# 1.net
KiCad netlist of a schematic drawn in EasyEDA
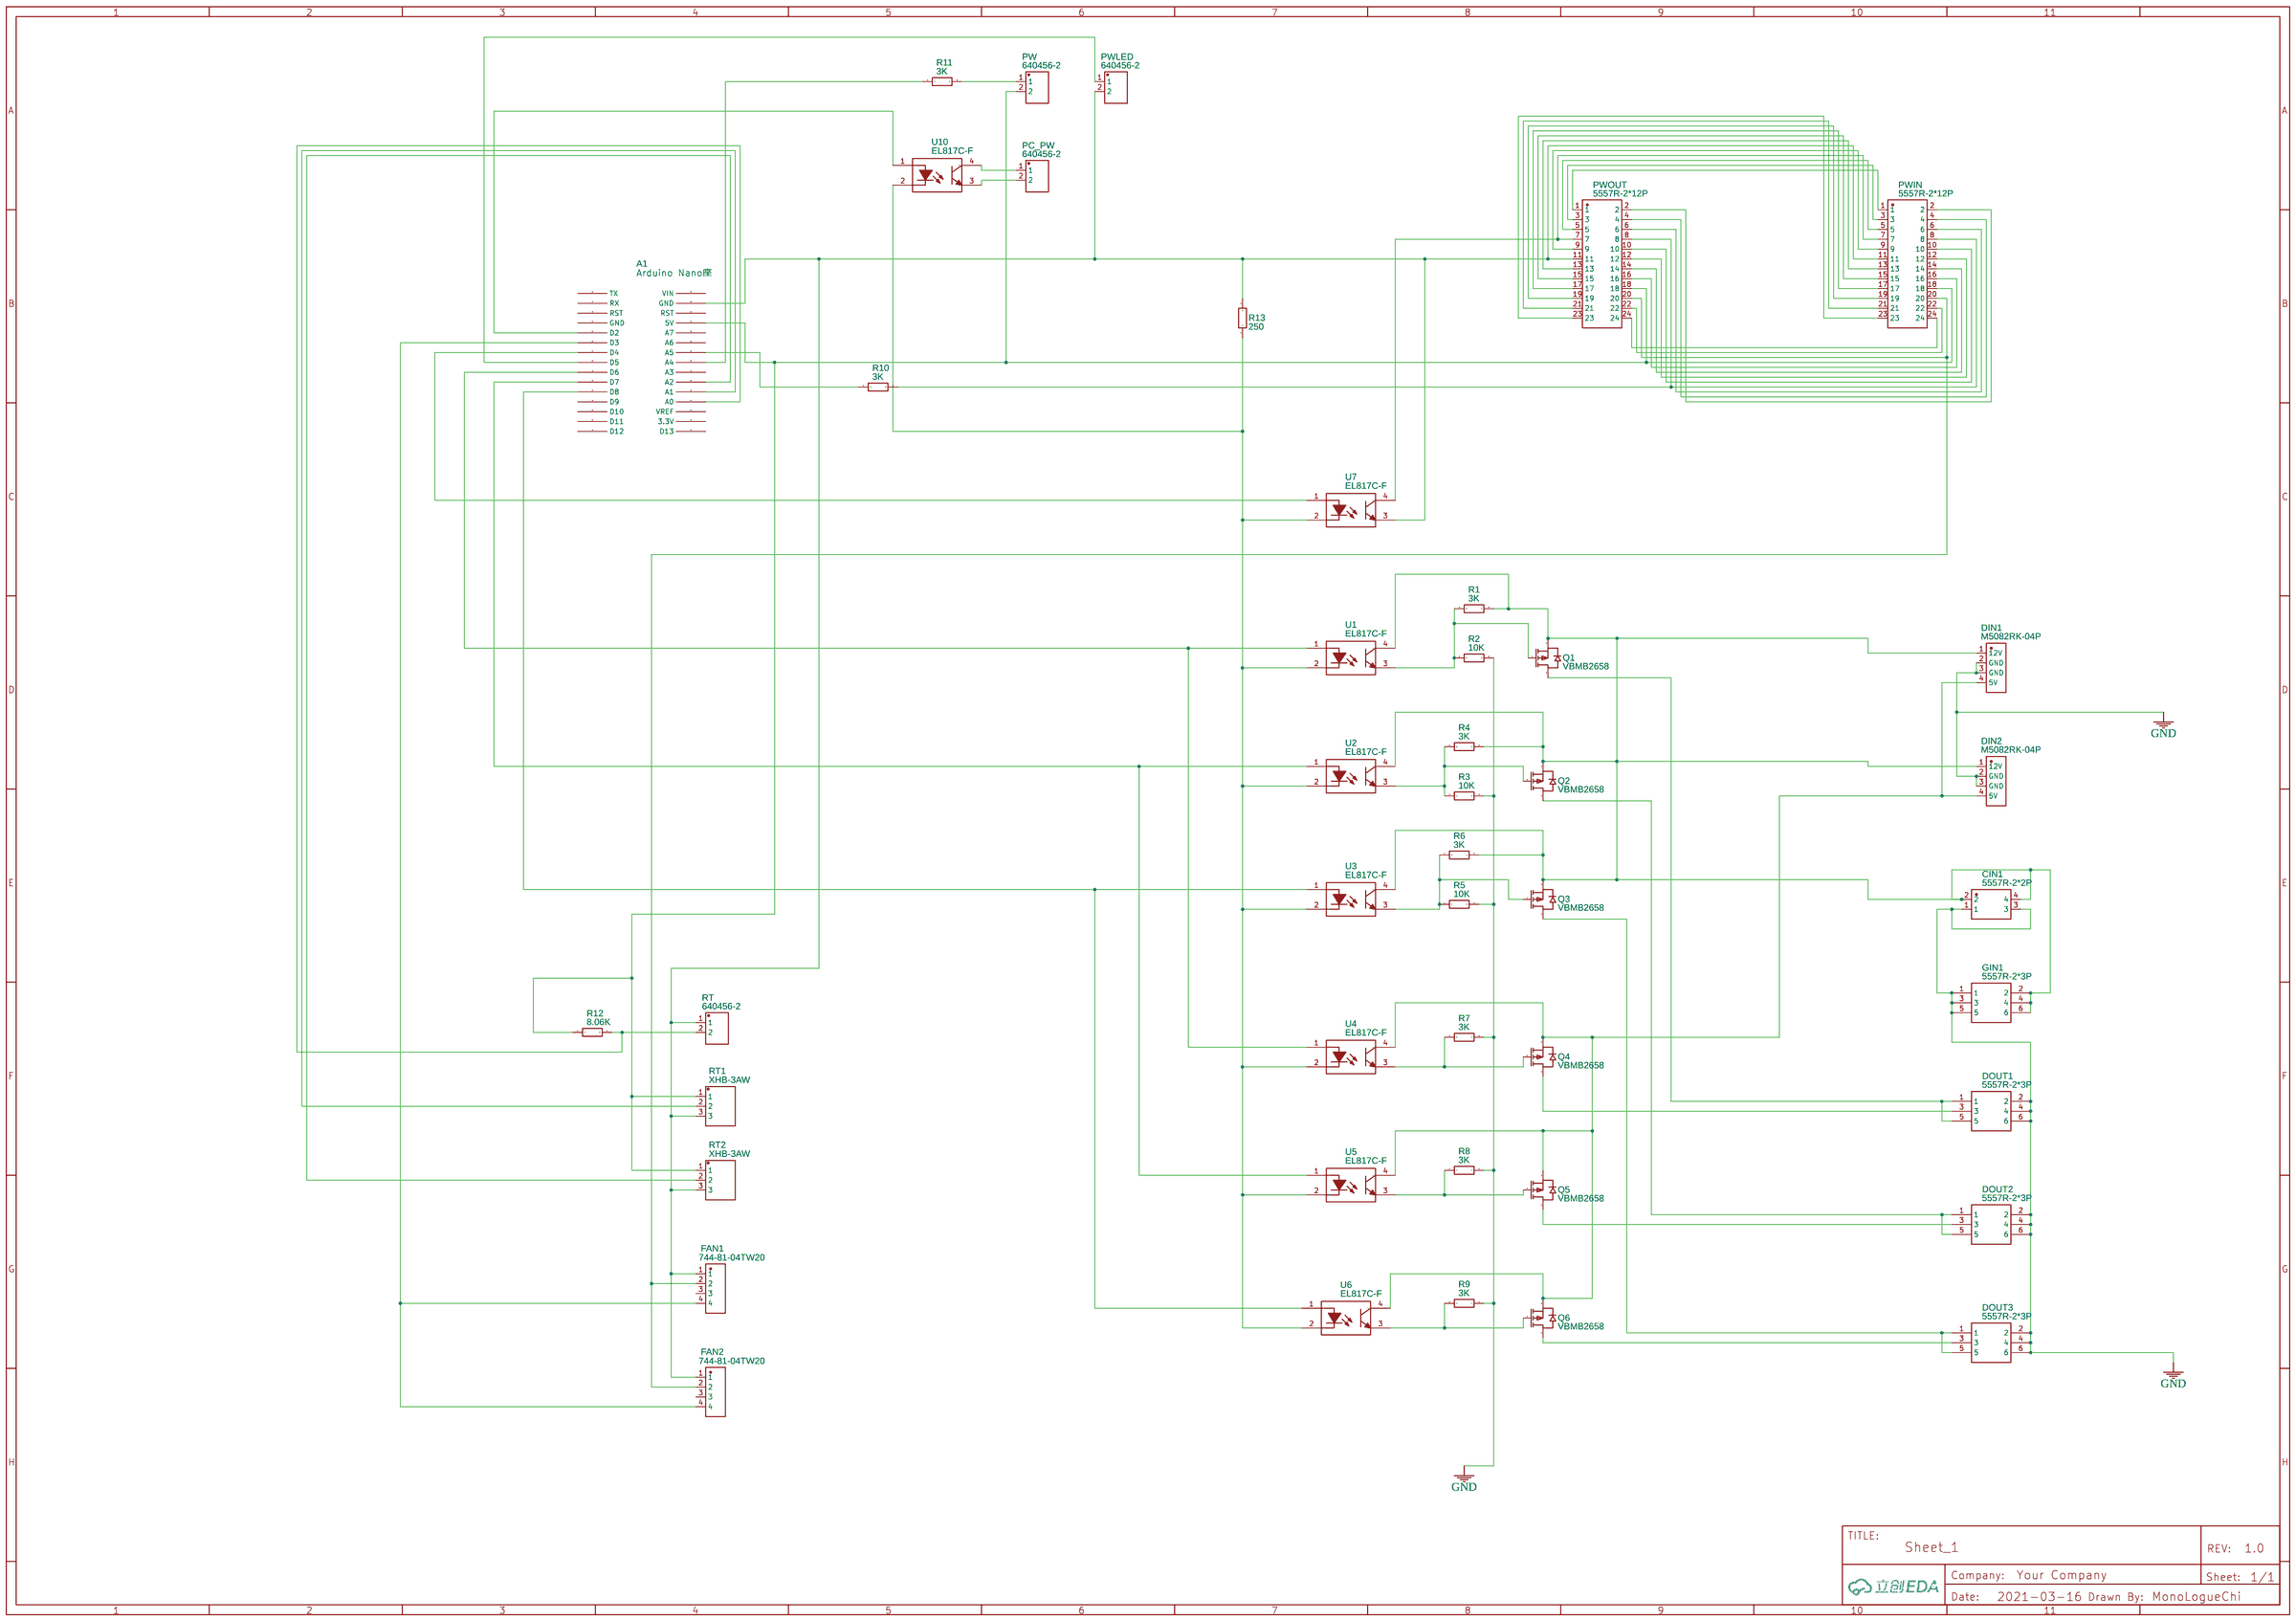
[diagram p0: schematic sheet]

(export (version "E")
  (design (tool "Eeschema 10.0.6"))
  (components
    (comp (ref "A1")
      (value "Arduino Nano座")
      (fields (field (name "BOM_Manufacturer Part") "Arduino Nano"))
      (libsource (lib "") (part "Arduino Nano座"))
    )
    (comp (ref "CIN1")
      (value "5557R-2*2P")
      (fields (field (name "BOM_Supplier Part") "C132446"))
      (libsource (lib "") (part "5557R-2*2P"))
    )
    (comp (ref "DIN1")
      (value "M5082RK-04P")
      (fields (field (name "BOM_Supplier Part") "C492552"))
      (libsource (lib "") (part "M5082RK-04P"))
    )
    (comp (ref "DIN2")
      (value "M5082RK-04P")
      (fields (field (name "BOM_Supplier Part") "C492552"))
      (libsource (lib "") (part "M5082RK-04P"))
    )
    (comp (ref "DOUT1")
      (value "5557R-2*3P")
      (fields (field (name "BOM_Supplier Part") "C124425"))
      (libsource (lib "") (part "5557R-2*3P"))
    )
    (comp (ref "DOUT2")
      (value "5557R-2*3P")
      (fields (field (name "BOM_Supplier Part") "C124425"))
      (libsource (lib "") (part "5557R-2*3P"))
    )
    (comp (ref "DOUT3")
      (value "5557R-2*3P")
      (fields (field (name "BOM_Supplier Part") "C124425"))
      (libsource (lib "") (part "5557R-2*3P"))
    )
    (comp (ref "FAN1")
      (value "744-81-04TW20")
      (fields (field (name "BOM_Supplier Part") "C402778"))
      (libsource (lib "") (part "744-81-04TW20"))
    )
    (comp (ref "FAN2")
      (value "744-81-04TW20")
      (fields (field (name "BOM_Supplier Part") "C402778"))
      (libsource (lib "") (part "744-81-04TW20"))
    )
    (comp (ref "GIN1")
      (value "5557R-2*3P")
      (fields (field (name "BOM_Supplier Part") "C124425"))
      (libsource (lib "") (part "5557R-2*3P_1"))
    )
    (comp (ref "PC_PW")
      (value "640456-2")
      (fields (field (name "BOM_Supplier Part") "C86502"))
      (libsource (lib "") (part "640456-2_1"))
    )
    (comp (ref "PW")
      (value "640456-2")
      (fields (field (name "BOM_Supplier Part") "C86502"))
      (libsource (lib "") (part "640456-2_2"))
    )
    (comp (ref "PWIN")
      (value "5557R-2*12P")
      (fields (field (name "BOM_Supplier Part") "C477841"))
      (libsource (lib "") (part "5557R-2*12P"))
    )
    (comp (ref "PWLED")
      (value "640456-2")
      (fields (field (name "BOM_Supplier Part") "C86502"))
      (libsource (lib "") (part "640456-2"))
    )
    (comp (ref "PWOUT")
      (value "5557R-2*12P")
      (fields (field (name "BOM_Supplier Part") "C477841"))
      (libsource (lib "") (part "5557R-2*12P_1"))
    )
    (comp (ref "Q1")
      (value "VBMB2658")
      (fields (field (name "BOM_Supplier Part") "C481043"))
      (libsource (lib "") (part "VBMB2658_1"))
    )
    (comp (ref "Q2")
      (value "VBMB2658")
      (fields (field (name "BOM_Supplier Part") "C481043"))
      (libsource (lib "") (part "VBMB2658_1"))
    )
    (comp (ref "Q3")
      (value "VBMB2658")
      (fields (field (name "BOM_Supplier Part") "C481043"))
      (libsource (lib "") (part "VBMB2658"))
    )
    (comp (ref "Q4")
      (value "VBMB2658")
      (fields (field (name "BOM_Supplier Part") "C481043"))
      (libsource (lib "") (part "VBMB2658"))
    )
    (comp (ref "Q5")
      (value "VBMB2658")
      (fields (field (name "BOM_Supplier Part") "C481043"))
      (libsource (lib "") (part "VBMB2658"))
    )
    (comp (ref "Q6")
      (value "VBMB2658")
      (fields (field (name "BOM_Supplier Part") "C481043"))
      (libsource (lib "") (part "VBMB2658"))
    )
    (comp (ref "R1")
      (value "3K")
      (fields
        (field (name "BOM_Manufacturer Part") "MFR0W4F3001A50")
        (field (name "BOM_Supplier Part") "C58606")
      )
      (libsource (lib "") (part "MFR0W4F3001A50"))
    )
    (comp (ref "R2")
      (value "10K")
      (fields
        (field (name "BOM_Manufacturer Part") "MFR0W4F1002A50")
        (field (name "BOM_Supplier Part") "C57436")
      )
      (libsource (lib "") (part "MFR0W4F1002A50"))
    )
    (comp (ref "R3")
      (value "10K")
      (fields
        (field (name "BOM_Manufacturer Part") "MFR0W4F1002A50")
        (field (name "BOM_Supplier Part") "C57436")
      )
      (libsource (lib "") (part "MFR0W4F1002A50"))
    )
    (comp (ref "R4")
      (value "3K")
      (fields
        (field (name "BOM_Manufacturer Part") "MFR0W4F3001A50")
        (field (name "BOM_Supplier Part") "C58606")
      )
      (libsource (lib "") (part "MFR0W4F3001A50"))
    )
    (comp (ref "R5")
      (value "10K")
      (fields
        (field (name "BOM_Manufacturer Part") "MFR0W4F1002A50")
        (field (name "BOM_Supplier Part") "C57436")
      )
      (libsource (lib "") (part "MFR0W4F1002A50"))
    )
    (comp (ref "R6")
      (value "3K")
      (fields
        (field (name "BOM_Manufacturer Part") "MFR0W4F3001A50")
        (field (name "BOM_Supplier Part") "C58606")
      )
      (libsource (lib "") (part "MFR0W4F3001A50"))
    )
    (comp (ref "R7")
      (value "3K")
      (fields
        (field (name "BOM_Manufacturer Part") "MFR0W4F3001A50")
        (field (name "BOM_Supplier Part") "C58606")
      )
      (libsource (lib "") (part "MFR0W4F3001A50"))
    )
    (comp (ref "R8")
      (value "3K")
      (fields
        (field (name "BOM_Manufacturer Part") "MFR0W4F3001A50")
        (field (name "BOM_Supplier Part") "C58606")
      )
      (libsource (lib "") (part "MFR0W4F3001A50"))
    )
    (comp (ref "R9")
      (value "3K")
      (fields
        (field (name "BOM_Manufacturer Part") "MFR0W4F3001A50")
        (field (name "BOM_Supplier Part") "C58606")
      )
      (libsource (lib "") (part "MFR0W4F3001A50"))
    )
    (comp (ref "R10")
      (value "3K")
      (fields
        (field (name "BOM_Manufacturer Part") "MFR0W4F3001A50")
        (field (name "BOM_Supplier Part") "C58606")
      )
      (libsource (lib "") (part "MFR0W4F3001A50"))
    )
    (comp (ref "R11")
      (value "3K")
      (fields
        (field (name "BOM_Manufacturer Part") "MFR0W4F3001A50")
        (field (name "BOM_Supplier Part") "C58606")
      )
      (libsource (lib "") (part "MFR0W4F3001A50"))
    )
    (comp (ref "R12")
      (value "8.06K")
      (fields
        (field (name "BOM_Manufacturer Part") "RN16T28061F")
        (field (name "BOM_Supplier Part") "C172591")
      )
      (libsource (lib "") (part "RN16T28061F"))
    )
    (comp (ref "R13")
      (value "250")
      (fields
        (field (name "BOM_Manufacturer Part") "MFR-25FTE52-250R")
        (field (name "BOM_Supplier Part") "C172991")
      )
      (libsource (lib "") (part "MFR-25FTE52-250R"))
    )
    (comp (ref "RT")
      (value "640456-2")
      (fields (field (name "BOM_Supplier Part") "C86502"))
      (libsource (lib "") (part "640456-2_3"))
    )
    (comp (ref "RT1")
      (value "XHB-3AW")
      (fields (field (name "BOM_Supplier Part") "C95477"))
      (libsource (lib "") (part "XHB-3AW"))
    )
    (comp (ref "RT2")
      (value "XHB-3AW")
      (fields (field (name "BOM_Supplier Part") "C95477"))
      (libsource (lib "") (part "XHB-3AW"))
    )
    (comp (ref "U1")
      (value "EL817C-F")
      (fields (field (name "BOM_Supplier Part") "C5352"))
      (libsource (lib "") (part "EL817C-F"))
    )
    (comp (ref "U2")
      (value "EL817C-F")
      (fields (field (name "BOM_Supplier Part") "C5352"))
      (libsource (lib "") (part "EL817C-F"))
    )
    (comp (ref "U3")
      (value "EL817C-F")
      (fields (field (name "BOM_Supplier Part") "C5352"))
      (libsource (lib "") (part "EL817C-F"))
    )
    (comp (ref "U4")
      (value "EL817C-F")
      (fields (field (name "BOM_Supplier Part") "C5352"))
      (libsource (lib "") (part "EL817C-F"))
    )
    (comp (ref "U5")
      (value "EL817C-F")
      (fields (field (name "BOM_Supplier Part") "C5352"))
      (libsource (lib "") (part "EL817C-F"))
    )
    (comp (ref "U6")
      (value "EL817C-F")
      (fields (field (name "BOM_Supplier Part") "C5352"))
      (libsource (lib "") (part "EL817C-F"))
    )
    (comp (ref "U7")
      (value "EL817C-F")
      (fields (field (name "BOM_Supplier Part") "C5352"))
      (libsource (lib "") (part "EL817C-F"))
    )
    (comp (ref "U10")
      (value "EL817C-F")
      (fields (field (name "BOM_Supplier Part") "C5352"))
      (libsource (lib "") (part "EL817C-F"))
    )
  )
  (nets
    (net (code "1") (name "GND") (class "Default")
      (node (ref "CIN1") (pin "1") (pinfunction "1_1") (pintype "unspecified"))
      (node (ref "CIN1") (pin "3") (pinfunction "3_3") (pintype "unspecified"))
      (node (ref "DIN1") (pin "2") (pinfunction "GND_2") (pintype "unspecified"))
      (node (ref "DIN1") (pin "3") (pinfunction "GND_3") (pintype "unspecified"))
      (node (ref "DIN2") (pin "2") (pinfunction "GND_2") (pintype "unspecified"))
      (node (ref "DIN2") (pin "3") (pinfunction "GND_3") (pintype "unspecified"))
      (node (ref "DOUT1") (pin "2") (pinfunction "2_2") (pintype "unspecified"))
      (node (ref "DOUT1") (pin "4") (pinfunction "4_4") (pintype "unspecified"))
      (node (ref "DOUT1") (pin "6") (pinfunction "6_6") (pintype "unspecified"))
      (node (ref "DOUT2") (pin "2") (pinfunction "2_2") (pintype "unspecified"))
      (node (ref "DOUT2") (pin "4") (pinfunction "4_4") (pintype "unspecified"))
      (node (ref "DOUT2") (pin "6") (pinfunction "6_6") (pintype "unspecified"))
      (node (ref "DOUT3") (pin "2") (pinfunction "2_2") (pintype "unspecified"))
      (node (ref "DOUT3") (pin "4") (pinfunction "4_4") (pintype "unspecified"))
      (node (ref "DOUT3") (pin "6") (pinfunction "6_6") (pintype "unspecified"))
      (node (ref "GIN1") (pin "1") (pinfunction "1_1") (pintype "unspecified"))
      (node (ref "GIN1") (pin "3") (pinfunction "3_3") (pintype "unspecified"))
      (node (ref "GIN1") (pin "5") (pinfunction "5_5") (pintype "unspecified"))
      (node (ref "R2") (pin "2") (pinfunction "2_2") (pintype "input"))
      (node (ref "R3") (pin "2") (pinfunction "2_2") (pintype "input"))
      (node (ref "R5") (pin "2") (pinfunction "2_2") (pintype "input"))
      (node (ref "R7") (pin "2") (pinfunction "2_2") (pintype "input"))
      (node (ref "R8") (pin "2") (pinfunction "2_2") (pintype "input"))
      (node (ref "R9") (pin "2") (pinfunction "2_2") (pintype "input"))
    )
    (net (code "2") (name "Net-(A1-5V)") (class "Default")
      (node (ref "A1") (pin "27") (pinfunction "5V_27") (pintype "unspecified"))
      (node (ref "PW") (pin "2") (pinfunction "2_2") (pintype "unspecified"))
      (node (ref "PWIN") (pin "18") (pinfunction "18_18") (pintype "unspecified"))
      (node (ref "PWOUT") (pin "18") (pinfunction "18_18") (pintype "unspecified"))
      (node (ref "R12") (pin "1") (pinfunction "1_1") (pintype "unspecified"))
      (node (ref "RT1") (pin "1") (pinfunction "1_1") (pintype "unspecified"))
      (node (ref "RT2") (pin "1") (pinfunction "1_1") (pintype "unspecified"))
    )
    (net (code "3") (name "Net-(A1-A0)") (class "Default")
      (node (ref "A1") (pin "19") (pinfunction "A0_19") (pintype "unspecified"))
      (node (ref "R12") (pin "2") (pinfunction "2_2") (pintype "unspecified"))
      (node (ref "RT") (pin "2") (pinfunction "2_2") (pintype "unspecified"))
    )
    (net (code "4") (name "Net-(A1-A1)") (class "Default")
      (node (ref "A1") (pin "20") (pinfunction "A1_20") (pintype "unspecified"))
      (node (ref "RT1") (pin "2") (pinfunction "2_2") (pintype "unspecified"))
    )
    (net (code "5") (name "Net-(A1-A2)") (class "Default")
      (node (ref "A1") (pin "21") (pinfunction "A2_21") (pintype "unspecified"))
      (node (ref "RT2") (pin "2") (pinfunction "2_2") (pintype "unspecified"))
    )
    (net (code "6") (name "Net-(A1-A4)") (class "Default")
      (node (ref "A1") (pin "23") (pinfunction "A4_23") (pintype "unspecified"))
      (node (ref "R11") (pin "1") (pinfunction "1_1") (pintype "input"))
    )
    (net (code "7") (name "Net-(A1-A5)") (class "Default")
      (node (ref "A1") (pin "24") (pinfunction "A5_24") (pintype "unspecified"))
      (node (ref "R10") (pin "1") (pinfunction "1_1") (pintype "input"))
    )
    (net (code "8") (name "Net-(A1-D2)") (class "Default")
      (node (ref "A1") (pin "5") (pinfunction "D2_5") (pintype "unspecified"))
      (node (ref "U10") (pin "1") (pinfunction "1_1") (pintype "unspecified"))
    )
    (net (code "9") (name "Net-(A1-D3)") (class "Default")
      (node (ref "A1") (pin "6") (pinfunction "D3_6") (pintype "unspecified"))
      (node (ref "FAN1") (pin "4") (pinfunction "4_4") (pintype "unspecified"))
      (node (ref "FAN2") (pin "4") (pinfunction "4_4") (pintype "unspecified"))
    )
    (net (code "10") (name "Net-(A1-D4)") (class "Default")
      (node (ref "A1") (pin "7") (pinfunction "D4_7") (pintype "unspecified"))
      (node (ref "U7") (pin "1") (pinfunction "1_1") (pintype "unspecified"))
    )
    (net (code "11") (name "Net-(A1-D5)") (class "Default")
      (node (ref "A1") (pin "8") (pinfunction "D5_8") (pintype "unspecified"))
      (node (ref "PWLED") (pin "1") (pinfunction "1_1") (pintype "unspecified"))
    )
    (net (code "12") (name "Net-(A1-D6)") (class "Default")
      (node (ref "A1") (pin "9") (pinfunction "D6_9") (pintype "unspecified"))
      (node (ref "U1") (pin "1") (pinfunction "1_1") (pintype "unspecified"))
      (node (ref "U4") (pin "1") (pinfunction "1_1") (pintype "unspecified"))
    )
    (net (code "13") (name "Net-(A1-D7)") (class "Default")
      (node (ref "A1") (pin "10") (pinfunction "D7_10") (pintype "unspecified"))
      (node (ref "U2") (pin "1") (pinfunction "1_1") (pintype "unspecified"))
      (node (ref "U5") (pin "1") (pinfunction "1_1") (pintype "unspecified"))
    )
    (net (code "14") (name "Net-(A1-D8)") (class "Default")
      (node (ref "A1") (pin "11") (pinfunction "D8_11") (pintype "unspecified"))
      (node (ref "U3") (pin "1") (pinfunction "1_1") (pintype "unspecified"))
      (node (ref "U6") (pin "1") (pinfunction "1_1") (pintype "unspecified"))
    )
    (net (code "15") (name "Net-(A1-GND-Pad29)") (class "Default")
      (node (ref "A1") (pin "29") (pinfunction "GND_29") (pintype "unspecified"))
      (node (ref "FAN1") (pin "1") (pinfunction "1_1") (pintype "unspecified"))
      (node (ref "FAN2") (pin "1") (pinfunction "1_1") (pintype "unspecified"))
      (node (ref "PWIN") (pin "11") (pinfunction "11_11") (pintype "unspecified"))
      (node (ref "PWLED") (pin "2") (pinfunction "2_2") (pintype "unspecified"))
      (node (ref "PWOUT") (pin "11") (pinfunction "11_11") (pintype "unspecified"))
      (node (ref "R13") (pin "1") (pinfunction "1_1") (pintype "unspecified"))
      (node (ref "RT") (pin "1") (pinfunction "1_1") (pintype "unspecified"))
      (node (ref "RT1") (pin "3") (pinfunction "3_3") (pintype "unspecified"))
      (node (ref "RT2") (pin "3") (pinfunction "3_3") (pintype "unspecified"))
      (node (ref "U7") (pin "3") (pinfunction "3_3") (pintype "unspecified"))
    )
    (net (code "16") (name "Net-(DIN1-5V)") (class "Default")
      (node (ref "DIN1") (pin "4") (pinfunction "5V_4") (pintype "unspecified"))
      (node (ref "DIN2") (pin "4") (pinfunction "5V_4") (pintype "unspecified"))
      (node (ref "Q4") (pin "3") (pinfunction "S_3") (pintype "unspecified"))
      (node (ref "Q5") (pin "3") (pinfunction "S_3") (pintype "unspecified"))
      (node (ref "Q6") (pin "3") (pinfunction "S_3") (pintype "unspecified"))
      (node (ref "U4") (pin "4") (pinfunction "4_4") (pintype "unspecified"))
      (node (ref "U5") (pin "4") (pinfunction "4_4") (pintype "unspecified"))
      (node (ref "U6") (pin "4") (pinfunction "4_4") (pintype "unspecified"))
    )
    (net (code "17") (name "Net-(DIN1-12V)") (class "Default")
      (node (ref "CIN1") (pin "2") (pinfunction "2_2") (pintype "unspecified"))
      (node (ref "CIN1") (pin "4") (pinfunction "4_4") (pintype "unspecified"))
      (node (ref "DIN1") (pin "1") (pinfunction "12V_1") (pintype "unspecified"))
      (node (ref "DIN2") (pin "1") (pinfunction "12V_1") (pintype "unspecified"))
      (node (ref "GIN1") (pin "2") (pinfunction "2_2") (pintype "unspecified"))
      (node (ref "GIN1") (pin "4") (pinfunction "4_4") (pintype "unspecified"))
      (node (ref "GIN1") (pin "6") (pinfunction "6_6") (pintype "unspecified"))
      (node (ref "Q1") (pin "3") (pinfunction "S_3") (pintype "unspecified"))
      (node (ref "Q2") (pin "3") (pinfunction "S_3") (pintype "unspecified"))
      (node (ref "Q3") (pin "3") (pinfunction "S_3") (pintype "unspecified"))
      (node (ref "R1") (pin "2") (pinfunction "2_2") (pintype "input"))
      (node (ref "R4") (pin "2") (pinfunction "2_2") (pintype "input"))
      (node (ref "R6") (pin "2") (pinfunction "2_2") (pintype "input"))
      (node (ref "U1") (pin "4") (pinfunction "4_4") (pintype "unspecified"))
      (node (ref "U2") (pin "4") (pinfunction "4_4") (pintype "unspecified"))
      (node (ref "U3") (pin "4") (pinfunction "4_4") (pintype "unspecified"))
    )
    (net (code "18") (name "Net-(FAN1-Pad2)") (class "Default")
      (node (ref "FAN1") (pin "2") (pinfunction "2_2") (pintype "unspecified"))
      (node (ref "FAN2") (pin "2") (pinfunction "2_2") (pintype "unspecified"))
      (node (ref "PWIN") (pin "20") (pinfunction "20_20") (pintype "unspecified"))
      (node (ref "PWOUT") (pin "20") (pinfunction "20_20") (pintype "unspecified"))
    )
    (net (code "19") (name "Net-(PC_PW-Pad1)") (class "Default")
      (node (ref "PC_PW") (pin "1") (pinfunction "1_1") (pintype "unspecified"))
      (node (ref "U10") (pin "4") (pinfunction "4_4") (pintype "unspecified"))
    )
    (net (code "20") (name "Net-(PC_PW-Pad2)") (class "Default")
      (node (ref "PC_PW") (pin "2") (pinfunction "2_2") (pintype "unspecified"))
      (node (ref "U10") (pin "3") (pinfunction "3_3") (pintype "unspecified"))
    )
    (net (code "21") (name "Net-(PW-Pad1)") (class "Default")
      (node (ref "PW") (pin "1") (pinfunction "1_1") (pintype "unspecified"))
      (node (ref "R11") (pin "2") (pinfunction "2_2") (pintype "input"))
    )
    (net (code "22") (name "Net-(PWIN-Pad1)") (class "Default")
      (node (ref "PWIN") (pin "1") (pinfunction "1_1") (pintype "unspecified"))
      (node (ref "PWOUT") (pin "1") (pinfunction "1_1") (pintype "unspecified"))
    )
    (net (code "23") (name "Net-(PWIN-Pad2)") (class "Default")
      (node (ref "PWIN") (pin "2") (pinfunction "2_2") (pintype "unspecified"))
      (node (ref "PWOUT") (pin "2") (pinfunction "2_2") (pintype "unspecified"))
    )
    (net (code "24") (name "Net-(PWIN-Pad3)") (class "Default")
      (node (ref "PWIN") (pin "3") (pinfunction "3_3") (pintype "unspecified"))
      (node (ref "PWOUT") (pin "3") (pinfunction "3_3") (pintype "unspecified"))
    )
    (net (code "25") (name "Net-(PWIN-Pad4)") (class "Default")
      (node (ref "PWIN") (pin "4") (pinfunction "4_4") (pintype "unspecified"))
      (node (ref "PWOUT") (pin "4") (pinfunction "4_4") (pintype "unspecified"))
    )
    (net (code "26") (name "Net-(PWIN-Pad5)") (class "Default")
      (node (ref "PWIN") (pin "5") (pinfunction "5_5") (pintype "unspecified"))
      (node (ref "PWOUT") (pin "5") (pinfunction "5_5") (pintype "unspecified"))
    )
    (net (code "27") (name "Net-(PWIN-Pad6)") (class "Default")
      (node (ref "PWIN") (pin "6") (pinfunction "6_6") (pintype "unspecified"))
      (node (ref "PWOUT") (pin "6") (pinfunction "6_6") (pintype "unspecified"))
    )
    (net (code "28") (name "Net-(PWIN-Pad7)") (class "Default")
      (node (ref "PWIN") (pin "7") (pinfunction "7_7") (pintype "unspecified"))
      (node (ref "PWOUT") (pin "7") (pinfunction "7_7") (pintype "unspecified"))
      (node (ref "U7") (pin "4") (pinfunction "4_4") (pintype "unspecified"))
    )
    (net (code "29") (name "Net-(PWIN-Pad8)") (class "Default")
      (node (ref "PWIN") (pin "8") (pinfunction "8_8") (pintype "unspecified"))
      (node (ref "PWOUT") (pin "8") (pinfunction "8_8") (pintype "unspecified"))
      (node (ref "R10") (pin "2") (pinfunction "2_2") (pintype "input"))
    )
    (net (code "30") (name "Net-(PWIN-Pad9)") (class "Default")
      (node (ref "PWIN") (pin "9") (pinfunction "9_9") (pintype "unspecified"))
      (node (ref "PWOUT") (pin "9") (pinfunction "9_9") (pintype "unspecified"))
    )
    (net (code "31") (name "Net-(PWIN-Pad10)") (class "Default")
      (node (ref "PWIN") (pin "10") (pinfunction "10_10") (pintype "unspecified"))
      (node (ref "PWOUT") (pin "10") (pinfunction "10_10") (pintype "unspecified"))
    )
    (net (code "32") (name "Net-(PWIN-Pad12)") (class "Default")
      (node (ref "PWIN") (pin "12") (pinfunction "12_12") (pintype "unspecified"))
      (node (ref "PWOUT") (pin "12") (pinfunction "12_12") (pintype "unspecified"))
    )
    (net (code "33") (name "Net-(PWIN-Pad13)") (class "Default")
      (node (ref "PWIN") (pin "13") (pinfunction "13_13") (pintype "unspecified"))
      (node (ref "PWOUT") (pin "13") (pinfunction "13_13") (pintype "unspecified"))
    )
    (net (code "34") (name "Net-(PWIN-Pad14)") (class "Default")
      (node (ref "PWIN") (pin "14") (pinfunction "14_14") (pintype "unspecified"))
      (node (ref "PWOUT") (pin "14") (pinfunction "14_14") (pintype "unspecified"))
    )
    (net (code "35") (name "Net-(PWIN-Pad15)") (class "Default")
      (node (ref "PWIN") (pin "15") (pinfunction "15_15") (pintype "unspecified"))
      (node (ref "PWOUT") (pin "15") (pinfunction "15_15") (pintype "unspecified"))
    )
    (net (code "36") (name "Net-(PWIN-Pad16)") (class "Default")
      (node (ref "PWIN") (pin "16") (pinfunction "16_16") (pintype "unspecified"))
      (node (ref "PWOUT") (pin "16") (pinfunction "16_16") (pintype "unspecified"))
    )
    (net (code "37") (name "Net-(PWIN-Pad17)") (class "Default")
      (node (ref "PWIN") (pin "17") (pinfunction "17_17") (pintype "unspecified"))
      (node (ref "PWOUT") (pin "17") (pinfunction "17_17") (pintype "unspecified"))
    )
    (net (code "38") (name "Net-(PWIN-Pad19)") (class "Default")
      (node (ref "PWIN") (pin "19") (pinfunction "19_19") (pintype "unspecified"))
      (node (ref "PWOUT") (pin "19") (pinfunction "19_19") (pintype "unspecified"))
    )
    (net (code "39") (name "Net-(PWIN-Pad21)") (class "Default")
      (node (ref "PWIN") (pin "21") (pinfunction "21_21") (pintype "unspecified"))
      (node (ref "PWOUT") (pin "21") (pinfunction "21_21") (pintype "unspecified"))
    )
    (net (code "40") (name "Net-(PWIN-Pad22)") (class "Default")
      (node (ref "PWIN") (pin "22") (pinfunction "22_22") (pintype "unspecified"))
      (node (ref "PWOUT") (pin "22") (pinfunction "22_22") (pintype "unspecified"))
    )
    (net (code "41") (name "Net-(PWIN-Pad23)") (class "Default")
      (node (ref "PWIN") (pin "23") (pinfunction "23_23") (pintype "unspecified"))
      (node (ref "PWOUT") (pin "23") (pinfunction "23_23") (pintype "unspecified"))
    )
    (net (code "42") (name "Net-(PWIN-Pad24)") (class "Default")
      (node (ref "PWIN") (pin "24") (pinfunction "24_24") (pintype "unspecified"))
      (node (ref "PWOUT") (pin "24") (pinfunction "24_24") (pintype "unspecified"))
    )
    (net (code "43") (name "Net-(Q1-D)") (class "Default")
      (node (ref "DOUT1") (pin "1") (pinfunction "1_1") (pintype "unspecified"))
      (node (ref "DOUT1") (pin "5") (pinfunction "5_5") (pintype "unspecified"))
      (node (ref "Q1") (pin "2") (pinfunction "D_2") (pintype "unspecified"))
    )
    (net (code "44") (name "Net-(Q1-G)") (class "Default")
      (node (ref "Q1") (pin "1") (pinfunction "G_1") (pintype "unspecified"))
      (node (ref "R1") (pin "1") (pinfunction "1_1") (pintype "input"))
      (node (ref "R2") (pin "1") (pinfunction "1_1") (pintype "input"))
      (node (ref "U1") (pin "3") (pinfunction "3_3") (pintype "unspecified"))
    )
    (net (code "45") (name "Net-(Q2-D)") (class "Default")
      (node (ref "DOUT2") (pin "1") (pinfunction "1_1") (pintype "unspecified"))
      (node (ref "DOUT2") (pin "5") (pinfunction "5_5") (pintype "unspecified"))
      (node (ref "Q2") (pin "2") (pinfunction "D_2") (pintype "unspecified"))
    )
    (net (code "46") (name "Net-(Q2-G)") (class "Default")
      (node (ref "Q2") (pin "1") (pinfunction "G_1") (pintype "unspecified"))
      (node (ref "R3") (pin "1") (pinfunction "1_1") (pintype "input"))
      (node (ref "R4") (pin "1") (pinfunction "1_1") (pintype "input"))
      (node (ref "U2") (pin "3") (pinfunction "3_3") (pintype "unspecified"))
    )
    (net (code "47") (name "Net-(Q3-D)") (class "Default")
      (node (ref "DOUT3") (pin "1") (pinfunction "1_1") (pintype "unspecified"))
      (node (ref "DOUT3") (pin "5") (pinfunction "5_5") (pintype "unspecified"))
      (node (ref "Q3") (pin "2") (pinfunction "D_2") (pintype "unspecified"))
    )
    (net (code "48") (name "Net-(Q3-G)") (class "Default")
      (node (ref "Q3") (pin "1") (pinfunction "G_1") (pintype "unspecified"))
      (node (ref "R5") (pin "1") (pinfunction "1_1") (pintype "input"))
      (node (ref "R6") (pin "1") (pinfunction "1_1") (pintype "input"))
      (node (ref "U3") (pin "3") (pinfunction "3_3") (pintype "unspecified"))
    )
    (net (code "49") (name "Net-(Q4-D)") (class "Default")
      (node (ref "DOUT1") (pin "3") (pinfunction "3_3") (pintype "unspecified"))
      (node (ref "Q4") (pin "2") (pinfunction "D_2") (pintype "unspecified"))
    )
    (net (code "50") (name "Net-(Q4-G)") (class "Default")
      (node (ref "Q4") (pin "1") (pinfunction "G_1") (pintype "unspecified"))
      (node (ref "R7") (pin "1") (pinfunction "1_1") (pintype "input"))
      (node (ref "U4") (pin "3") (pinfunction "3_3") (pintype "unspecified"))
    )
    (net (code "51") (name "Net-(Q5-D)") (class "Default")
      (node (ref "DOUT2") (pin "3") (pinfunction "3_3") (pintype "unspecified"))
      (node (ref "Q5") (pin "2") (pinfunction "D_2") (pintype "unspecified"))
    )
    (net (code "52") (name "Net-(Q5-G)") (class "Default")
      (node (ref "Q5") (pin "1") (pinfunction "G_1") (pintype "unspecified"))
      (node (ref "R8") (pin "1") (pinfunction "1_1") (pintype "input"))
      (node (ref "U5") (pin "3") (pinfunction "3_3") (pintype "unspecified"))
    )
    (net (code "53") (name "Net-(Q6-D)") (class "Default")
      (node (ref "DOUT3") (pin "3") (pinfunction "3_3") (pintype "unspecified"))
      (node (ref "Q6") (pin "2") (pinfunction "D_2") (pintype "unspecified"))
    )
    (net (code "54") (name "Net-(Q6-G)") (class "Default")
      (node (ref "Q6") (pin "1") (pinfunction "G_1") (pintype "unspecified"))
      (node (ref "R9") (pin "1") (pinfunction "1_1") (pintype "input"))
      (node (ref "U6") (pin "3") (pinfunction "3_3") (pintype "unspecified"))
    )
    (net (code "55") (name "Net-(R13-Pad2)") (class "Default")
      (node (ref "R13") (pin "2") (pinfunction "2_2") (pintype "unspecified"))
      (node (ref "U1") (pin "2") (pinfunction "2_2") (pintype "unspecified"))
      (node (ref "U10") (pin "2") (pinfunction "2_2") (pintype "unspecified"))
      (node (ref "U2") (pin "2") (pinfunction "2_2") (pintype "unspecified"))
      (node (ref "U3") (pin "2") (pinfunction "2_2") (pintype "unspecified"))
      (node (ref "U4") (pin "2") (pinfunction "2_2") (pintype "unspecified"))
      (node (ref "U5") (pin "2") (pinfunction "2_2") (pintype "unspecified"))
      (node (ref "U6") (pin "2") (pinfunction "2_2") (pintype "unspecified"))
      (node (ref "U7") (pin "2") (pinfunction "2_2") (pintype "unspecified"))
    )
    (net (code "56") (name "unconnected-(A1-3.3V-Pad17)") (class "Default")
      (node (ref "A1") (pin "17") (pinfunction "3.3V_17") (pintype "unspecified"))
    )
    (net (code "57") (name "unconnected-(A1-A3-Pad22)") (class "Default")
      (node (ref "A1") (pin "22") (pinfunction "A3_22") (pintype "unspecified"))
    )
    (net (code "58") (name "unconnected-(A1-A6-Pad25)") (class "Default")
      (node (ref "A1") (pin "25") (pinfunction "A6_25") (pintype "unspecified"))
    )
    (net (code "59") (name "unconnected-(A1-A7-Pad26)") (class "Default")
      (node (ref "A1") (pin "26") (pinfunction "A7_26") (pintype "unspecified"))
    )
    (net (code "60") (name "unconnected-(A1-D9-Pad12)") (class "Default")
      (node (ref "A1") (pin "12") (pinfunction "D9_12") (pintype "unspecified"))
    )
    (net (code "61") (name "unconnected-(A1-D10-Pad13)") (class "Default")
      (node (ref "A1") (pin "13") (pinfunction "D10_13") (pintype "unspecified"))
    )
    (net (code "62") (name "unconnected-(A1-D11-Pad14)") (class "Default")
      (node (ref "A1") (pin "14") (pinfunction "D11_14") (pintype "unspecified"))
    )
    (net (code "63") (name "unconnected-(A1-D12-Pad15)") (class "Default")
      (node (ref "A1") (pin "15") (pinfunction "D12_15") (pintype "unspecified"))
    )
    (net (code "64") (name "unconnected-(A1-D13-Pad16)") (class "Default")
      (node (ref "A1") (pin "16") (pinfunction "D13_16") (pintype "unspecified"))
    )
    (net (code "65") (name "unconnected-(A1-GND-Pad4)") (class "Default")
      (node (ref "A1") (pin "4") (pinfunction "GND_4") (pintype "unspecified"))
    )
    (net (code "66") (name "unconnected-(A1-RST-Pad3)") (class "Default")
      (node (ref "A1") (pin "3") (pinfunction "RST_3") (pintype "unspecified"))
    )
    (net (code "67") (name "unconnected-(A1-RST-Pad28)") (class "Default")
      (node (ref "A1") (pin "28") (pinfunction "RST_28") (pintype "unspecified"))
    )
    (net (code "68") (name "unconnected-(A1-RX-Pad2)") (class "Default")
      (node (ref "A1") (pin "2") (pinfunction "RX_2") (pintype "unspecified"))
    )
    (net (code "69") (name "unconnected-(A1-TX-Pad1)") (class "Default")
      (node (ref "A1") (pin "1") (pinfunction "TX_1") (pintype "unspecified"))
    )
    (net (code "70") (name "unconnected-(A1-VIN-Pad30)") (class "Default")
      (node (ref "A1") (pin "30") (pinfunction "VIN_30") (pintype "unspecified"))
    )
    (net (code "71") (name "unconnected-(A1-VREF-Pad18)") (class "Default")
      (node (ref "A1") (pin "18") (pinfunction "VREF_18") (pintype "unspecified"))
    )
    (net (code "72") (name "unconnected-(FAN1-Pad3)") (class "Default")
      (node (ref "FAN1") (pin "3") (pinfunction "3_3") (pintype "unspecified"))
    )
    (net (code "73") (name "unconnected-(FAN2-Pad3)") (class "Default")
      (node (ref "FAN2") (pin "3") (pinfunction "3_3") (pintype "unspecified"))
    )
  )
)
